# ict_v361.net
KiCad netlist of a schematic drawn in EAGLE
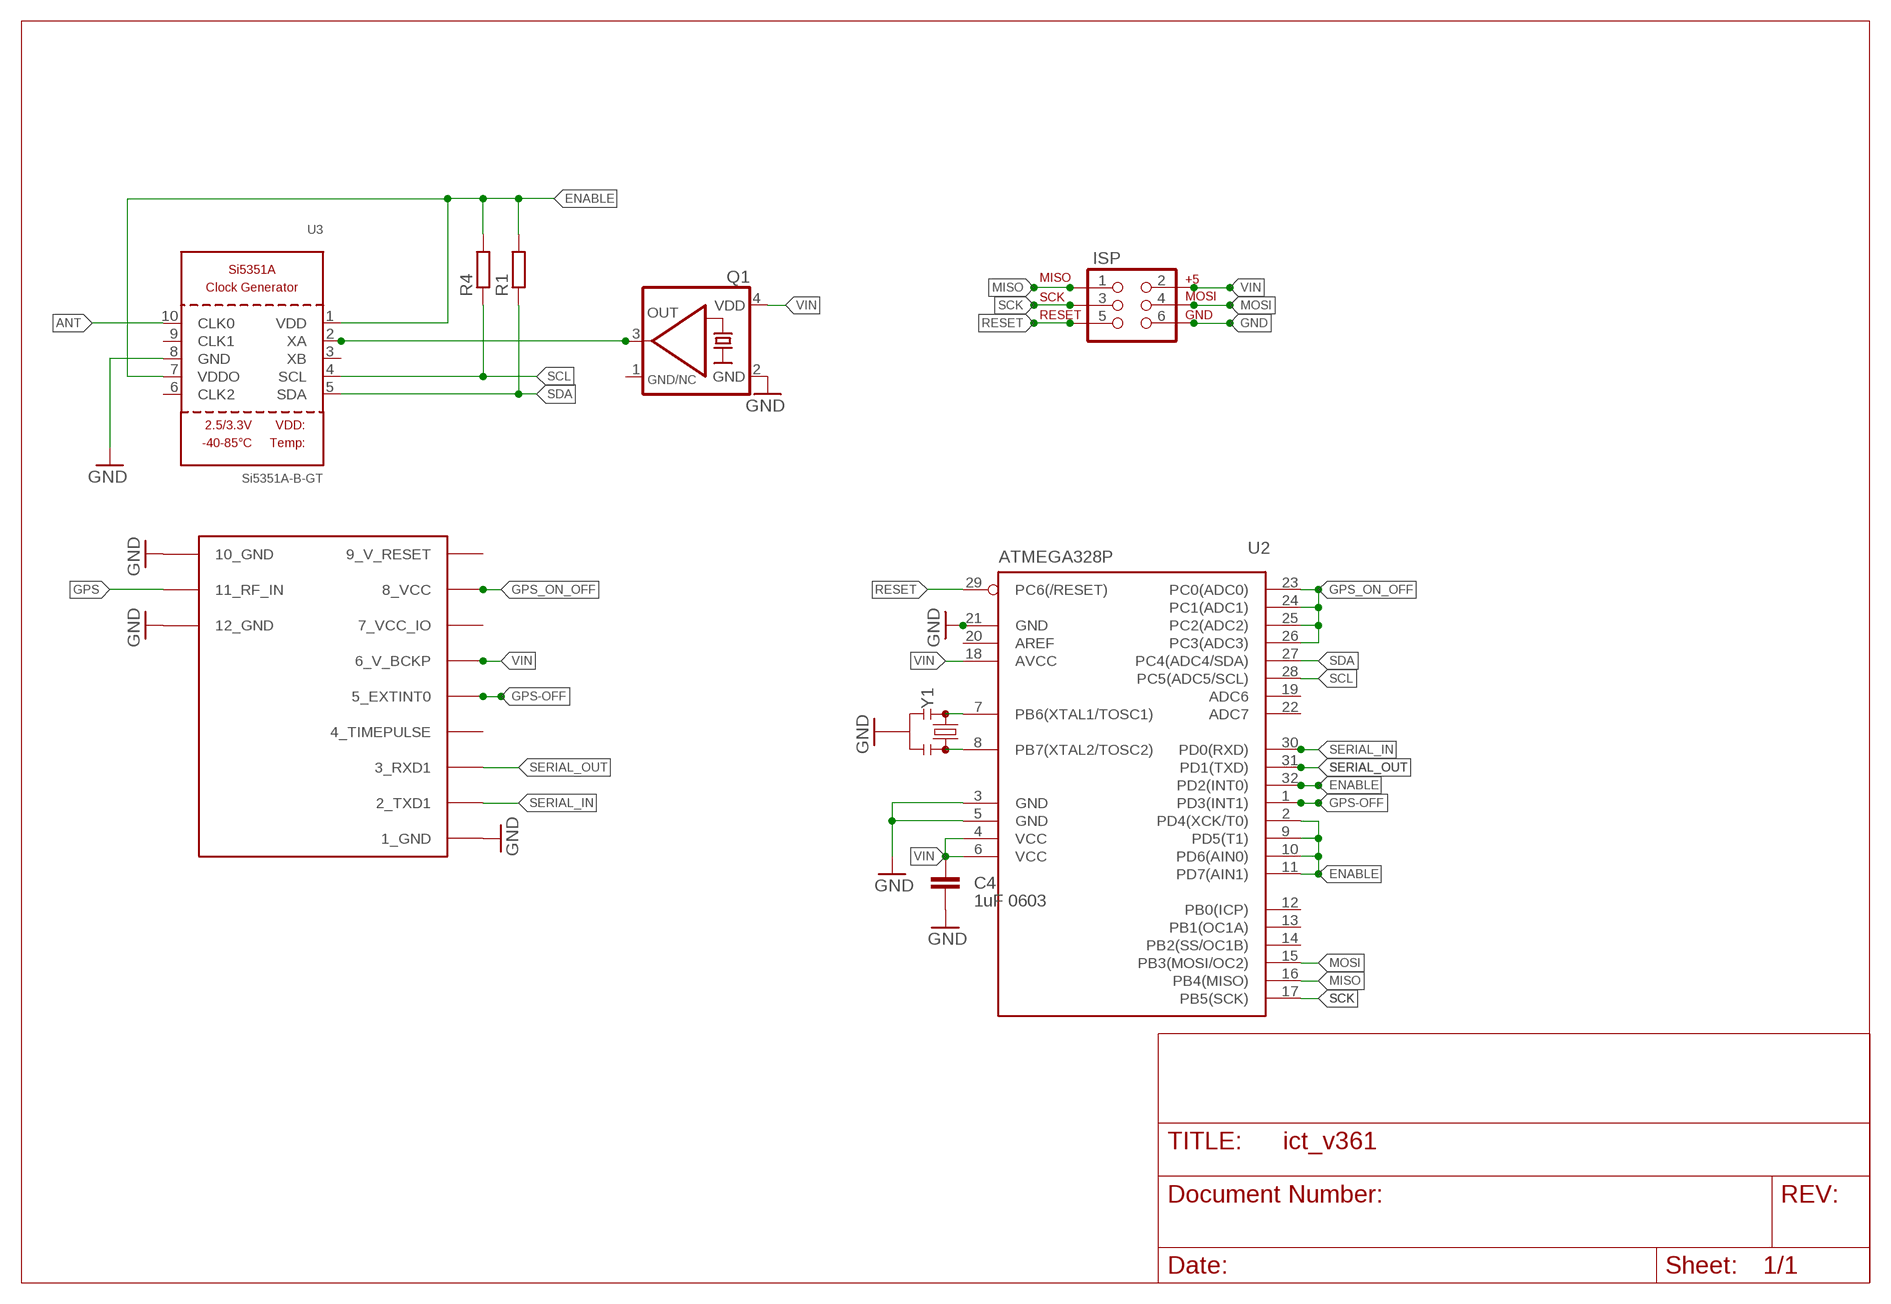
[diagram p0: schematic, sheet 1]

(export (version "E")
  (design (tool "Eeschema 10.0.6"))
  (components
    (comp (ref "C4")
      (value "1uF 0603")
      (footprint "eagle-import:C0603K")
      (libsource (lib "eagle-import") (part "C-EUC0603K"))
    )
    (comp (ref "ISP")
      (value "AVR_SPI_PRG_6PTH")
      (footprint "eagle-import:2X3")
      (libsource (lib "eagle-import") (part "AVR_SPI_PRG_6PTH"))
    )
    (comp (ref "Q1")
      (value "KXO-TCXO-CMOS-84")
      (footprint "eagle-import:3.2X2.5_KXO-84-TCXO")
      (libsource (lib "eagle-import") (part "KXO-TCXO-CMOS-84"))
    )
    (comp (ref "R1")
      (value "R-EU_R0603")
      (footprint "eagle-import:R0603")
      (libsource (lib "eagle-import") (part "R-EU_R0603"))
    )
    (comp (ref "R4")
      (value "R-EU_R0603")
      (footprint "eagle-import:R0603")
      (libsource (lib "eagle-import") (part "R-EU_R0603"))
    )
    (comp (ref "U$2")
      (value "UBLOX_MAX")
      (footprint "eagle-import:UBLOX_MAX")
      (libsource (lib "eagle-import") (part "UBLOX_MAX"))
    )
    (comp (ref "U2")
      (value "ATMEGA328P")
      (footprint "eagle-import:TQFP32-08")
      (fields (field (name "MPN") "ATMEGA8-16AU"))
      (libsource (lib "eagle-import") (part "MEGA8-AI"))
    )
    (comp (ref "U3")
      (value "Si5351A-B-GT")
      (footprint "eagle-import:MSOP10")
      (libsource (lib "eagle-import") (part "SI5351A"))
    )
    (comp (ref "Y1")
      (value "RESONATORSMD-4.5X2.0")
      (footprint "eagle-import:RESONATOR-SMD-4.5X2.0")
      (libsource (lib "eagle-import") (part "RESONATORSMD-4.5X2.0"))
    )
  )
  (nets
    (net (code "1") (name "/7_VCC_IO") (class "Default")
      (node (ref "U$2") (pin "7_VCC_IO") (pinfunction "7_VCC_IO_7_VCC_IO") (pintype "power_in"))
    )
    (net (code "2") (name "/9_V_RESET") (class "Default")
      (node (ref "U$2") (pin "9_V_RESET") (pinfunction "9_V_RESET_9_V_RESET") (pintype "power_in"))
    )
    (net (code "3") (name "/GND{slash}NC") (class "Default")
      (node (ref "Q1") (pin "1") (pinfunction "GND/NC_1") (pintype "power_in"))
    )
    (net (code "4") (name "ANT") (class "Default")
      (node (ref "U3") (pin "10") (pinfunction "CLK0_10") (pintype "output"))
    )
    (net (code "5") (name "ENABLE") (class "Default")
      (node (ref "R1") (pin "2") (pinfunction "2_2") (pintype "passive"))
      (node (ref "R4") (pin "2") (pinfunction "2_2") (pintype "passive"))
      (node (ref "U2") (pin "10") (pinfunction "PD6(AIN0)_10") (pintype "bidirectional"))
      (node (ref "U2") (pin "11") (pinfunction "PD7(AIN1)_11") (pintype "bidirectional"))
      (node (ref "U2") (pin "2") (pinfunction "PD4(XCK/T0)_2") (pintype "bidirectional"))
      (node (ref "U2") (pin "32") (pinfunction "PD2(INT0)_32") (pintype "bidirectional"))
      (node (ref "U2") (pin "9") (pinfunction "PD5(T1)_9") (pintype "bidirectional"))
      (node (ref "U3") (pin "1") (pinfunction "VDD_1") (pintype "power_in"))
      (node (ref "U3") (pin "7") (pinfunction "VDDO_7") (pintype "power_in"))
    )
    (net (code "6") (name "GND") (class "Default")
      (node (ref "C4") (pin "2") (pinfunction "2_2") (pintype "passive"))
      (node (ref "ISP") (pin "6") (pinfunction "6_6") (pintype "passive"))
      (node (ref "Q1") (pin "2") (pinfunction "GND_2") (pintype "power_in"))
      (node (ref "U$2") (pin "10_GND") (pinfunction "10_GND_10_GND") (pintype "power_in"))
      (node (ref "U$2") (pin "12_GND") (pinfunction "12_GND_12_GND") (pintype "power_in"))
      (node (ref "U$2") (pin "1_GND") (pinfunction "1_GND_1_GND") (pintype "power_in"))
      (node (ref "U2") (pin "21") (pinfunction "GND_21") (pintype "power_in"))
      (node (ref "U2") (pin "3") (pinfunction "GND_3") (pintype "power_in"))
      (node (ref "U2") (pin "5") (pinfunction "GND_5") (pintype "power_in"))
      (node (ref "U3") (pin "8") (pinfunction "GND_8") (pintype "power_in"))
      (node (ref "Y1") (pin "2") (pinfunction "2_2") (pintype "passive"))
    )
    (net (code "7") (name "GPS") (class "Default")
      (node (ref "U$2") (pin "11_RF_IN") (pinfunction "11_RF_IN_11_RF_IN") (pintype "bidirectional"))
    )
    (net (code "8") (name "GPS-OFF") (class "Default")
      (node (ref "U$2") (pin "5_EXTINT0") (pinfunction "5_EXTINT0_5_EXTINT0") (pintype "bidirectional"))
      (node (ref "U2") (pin "1") (pinfunction "PD3(INT1)_1") (pintype "bidirectional"))
    )
    (net (code "9") (name "GPS_ON_OFF") (class "Default")
      (node (ref "U$2") (pin "8_VCC") (pinfunction "8_VCC_8_VCC") (pintype "power_in"))
      (node (ref "U2") (pin "23") (pinfunction "PC0(ADC0)_23") (pintype "bidirectional"))
      (node (ref "U2") (pin "24") (pinfunction "PC1(ADC1)_24") (pintype "bidirectional"))
      (node (ref "U2") (pin "25") (pinfunction "PC2(ADC2)_25") (pintype "bidirectional"))
      (node (ref "U2") (pin "26") (pinfunction "PC3(ADC3)_26") (pintype "bidirectional"))
    )
    (net (code "10") (name "MISO") (class "Default")
      (node (ref "ISP") (pin "1") (pinfunction "1_1") (pintype "passive"))
      (node (ref "U2") (pin "16") (pinfunction "PB4(MISO)_16") (pintype "bidirectional"))
    )
    (net (code "11") (name "MOSI") (class "Default")
      (node (ref "ISP") (pin "4") (pinfunction "4_4") (pintype "passive"))
      (node (ref "U2") (pin "15") (pinfunction "PB3(MOSI/OC2)_15") (pintype "bidirectional"))
    )
    (net (code "12") (name "Net-(Q1-OUT)") (class "Default")
      (node (ref "Q1") (pin "3") (pinfunction "OUT_3") (pintype "output"))
      (node (ref "U3") (pin "2") (pinfunction "XA_2") (pintype "input"))
    )
    (net (code "13") (name "Net-(U2-PB6(XTAL1{slash}TOSC1))") (class "Default")
      (node (ref "U2") (pin "7") (pinfunction "PB6(XTAL1/TOSC1)_7") (pintype "bidirectional"))
      (node (ref "Y1") (pin "1") (pinfunction "1_1") (pintype "passive"))
    )
    (net (code "14") (name "Net-(U2-PB7(XTAL2{slash}TOSC2))") (class "Default")
      (node (ref "U2") (pin "8") (pinfunction "PB7(XTAL2/TOSC2)_8") (pintype "bidirectional"))
      (node (ref "Y1") (pin "3") (pinfunction "3_3") (pintype "passive"))
    )
    (net (code "15") (name "RESET") (class "Default")
      (node (ref "ISP") (pin "5") (pinfunction "5_5") (pintype "passive"))
      (node (ref "U2") (pin "29") (pinfunction "PC6(/RESET)_29") (pintype "bidirectional"))
    )
    (net (code "16") (name "SCK") (class "Default")
      (node (ref "ISP") (pin "3") (pinfunction "3_3") (pintype "passive"))
      (node (ref "U2") (pin "17") (pinfunction "PB5(SCK)_17") (pintype "bidirectional"))
    )
    (net (code "17") (name "SCL") (class "Default")
      (node (ref "R4") (pin "1") (pinfunction "1_1") (pintype "passive"))
      (node (ref "U2") (pin "28") (pinfunction "PC5(ADC5/SCL)_28") (pintype "bidirectional"))
      (node (ref "U3") (pin "4") (pinfunction "SCL_4") (pintype "input"))
    )
    (net (code "18") (name "SDA") (class "Default")
      (node (ref "R1") (pin "1") (pinfunction "1_1") (pintype "passive"))
      (node (ref "U2") (pin "27") (pinfunction "PC4(ADC4/SDA)_27") (pintype "bidirectional"))
      (node (ref "U3") (pin "5") (pinfunction "SDA_5") (pintype "bidirectional"))
    )
    (net (code "19") (name "SERIAL_IN") (class "Default")
      (node (ref "U$2") (pin "2_TXD1") (pinfunction "2_TXD1_2_TXD1") (pintype "bidirectional"))
      (node (ref "U2") (pin "30") (pinfunction "PD0(RXD)_30") (pintype "bidirectional"))
    )
    (net (code "20") (name "SERIAL_OUT") (class "Default")
      (node (ref "U$2") (pin "3_RXD1") (pinfunction "3_RXD1_3_RXD1") (pintype "bidirectional"))
      (node (ref "U2") (pin "31") (pinfunction "PD1(TXD)_31") (pintype "bidirectional"))
    )
    (net (code "21") (name "VIN") (class "Default")
      (node (ref "C4") (pin "1") (pinfunction "1_1") (pintype "passive"))
      (node (ref "ISP") (pin "2") (pinfunction "2_2") (pintype "passive"))
      (node (ref "Q1") (pin "4") (pinfunction "VDD_4") (pintype "power_in"))
      (node (ref "U$2") (pin "6_V_BCKP") (pinfunction "6_V_BCKP_6_V_BCKP") (pintype "bidirectional"))
      (node (ref "U2") (pin "18") (pinfunction "AVCC_18") (pintype "power_in"))
      (node (ref "U2") (pin "4") (pinfunction "VCC_4") (pintype "power_in"))
      (node (ref "U2") (pin "6") (pinfunction "VCC_6") (pintype "power_in"))
    )
    (net (code "22") (name "unconnected-(U$2-Pad4_TIMEPULSE)") (class "Default")
      (node (ref "U$2") (pin "4_TIMEPULSE") (pinfunction "4_TIMEPULSE_4_TIMEPULSE") (pintype "bidirectional"))
    )
    (net (code "23") (name "unconnected-(U2-ADC6-Pad19)") (class "Default")
      (node (ref "U2") (pin "19") (pinfunction "ADC6_19") (pintype "bidirectional"))
    )
    (net (code "24") (name "unconnected-(U2-ADC7-Pad22)") (class "Default")
      (node (ref "U2") (pin "22") (pinfunction "ADC7_22") (pintype "bidirectional"))
    )
    (net (code "25") (name "unconnected-(U2-AREF-Pad20)") (class "Default")
      (node (ref "U2") (pin "20") (pinfunction "AREF_20") (pintype "passive"))
    )
    (net (code "26") (name "unconnected-(U2-PB0(ICP)-Pad12)") (class "Default")
      (node (ref "U2") (pin "12") (pinfunction "PB0(ICP)_12") (pintype "bidirectional"))
    )
    (net (code "27") (name "unconnected-(U2-PB1(OC1A)-Pad13)") (class "Default")
      (node (ref "U2") (pin "13") (pinfunction "PB1(OC1A)_13") (pintype "bidirectional"))
    )
    (net (code "28") (name "unconnected-(U2-PB2(SS{slash}OC1B)-Pad14)") (class "Default")
      (node (ref "U2") (pin "14") (pinfunction "PB2(SS/OC1B)_14") (pintype "bidirectional"))
    )
    (net (code "29") (name "unconnected-(U3-CLK1-Pad9)") (class "Default")
      (node (ref "U3") (pin "9") (pinfunction "CLK1_9") (pintype "output"))
    )
    (net (code "30") (name "unconnected-(U3-CLK2-Pad6)") (class "Default")
      (node (ref "U3") (pin "6") (pinfunction "CLK2_6") (pintype "output"))
    )
    (net (code "31") (name "unconnected-(U3-XB-Pad3)") (class "Default")
      (node (ref "U3") (pin "3") (pinfunction "XB_3") (pintype "input"))
    )
  )
)
